# qo-100-i2c-buffer.net
KiCad netlist of a schematic drawn in EAGLE
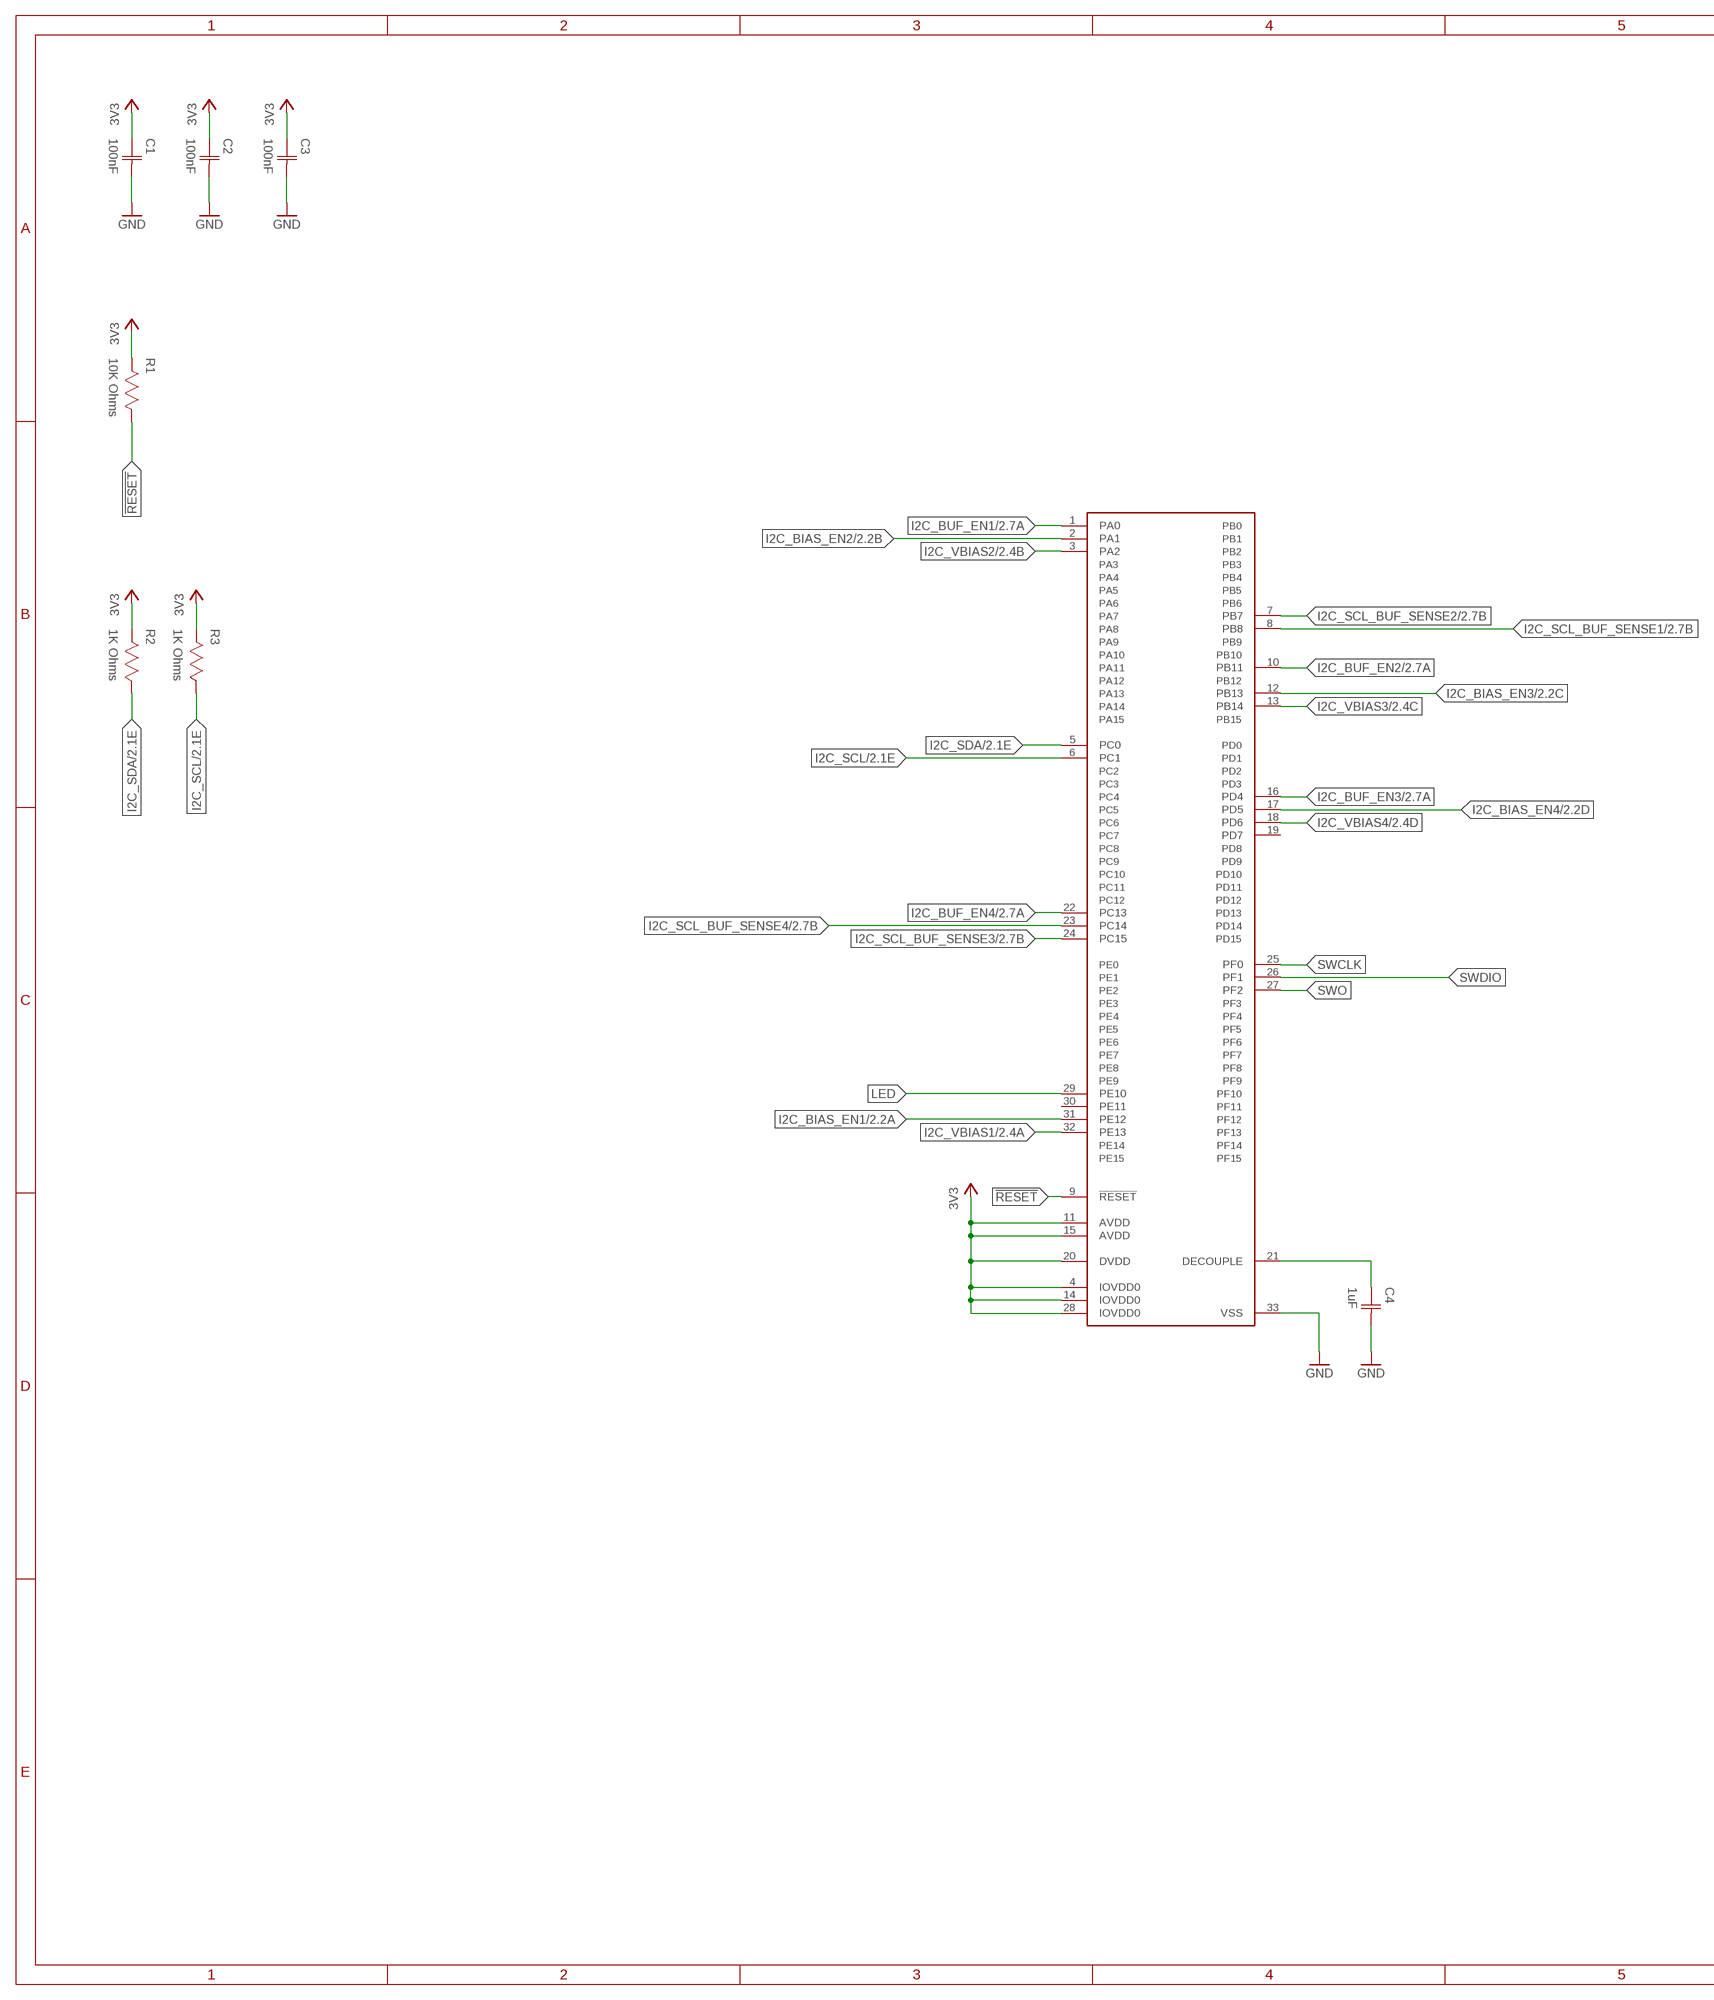
[diagram p0: schematic, sheet 1, part 1 of 2]
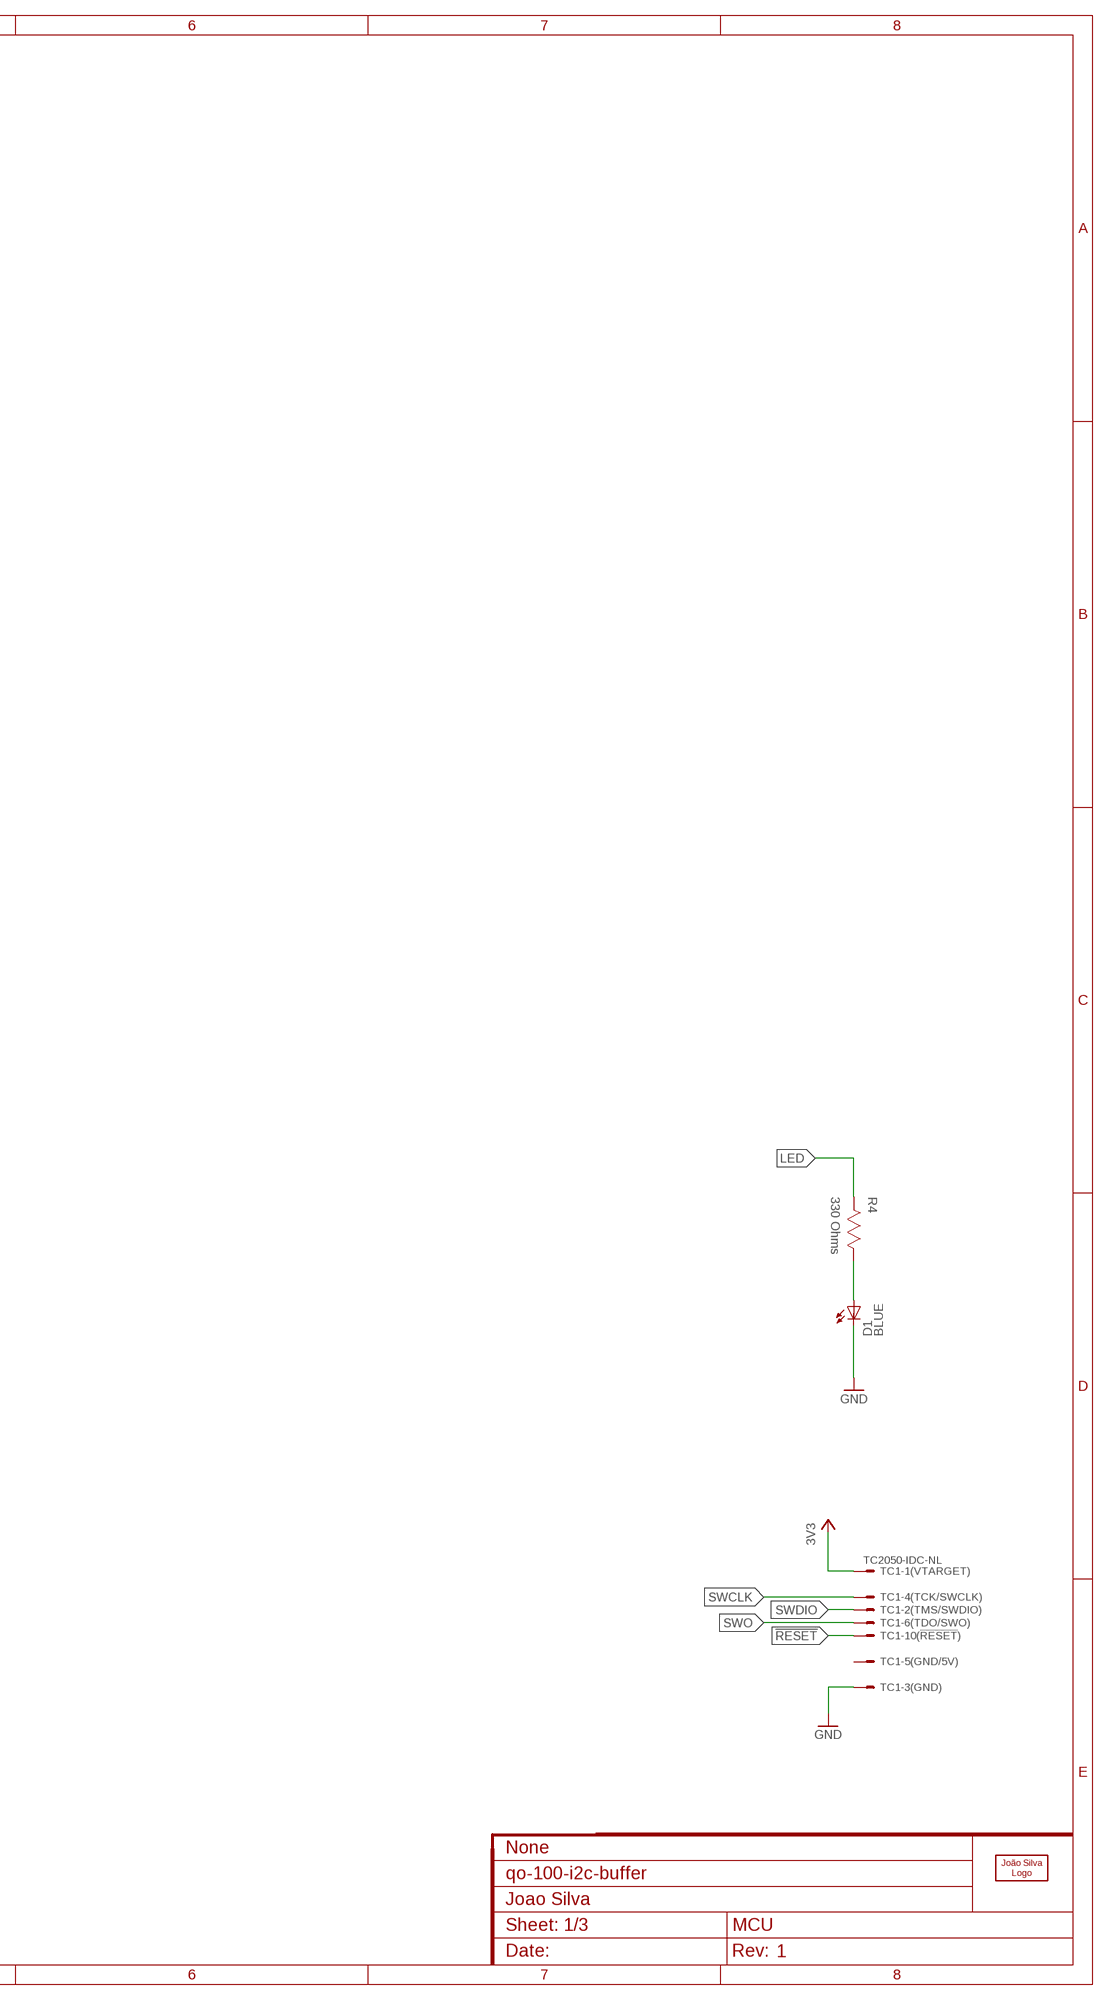
[diagram p1: schematic, sheet 1, part 2 of 2]
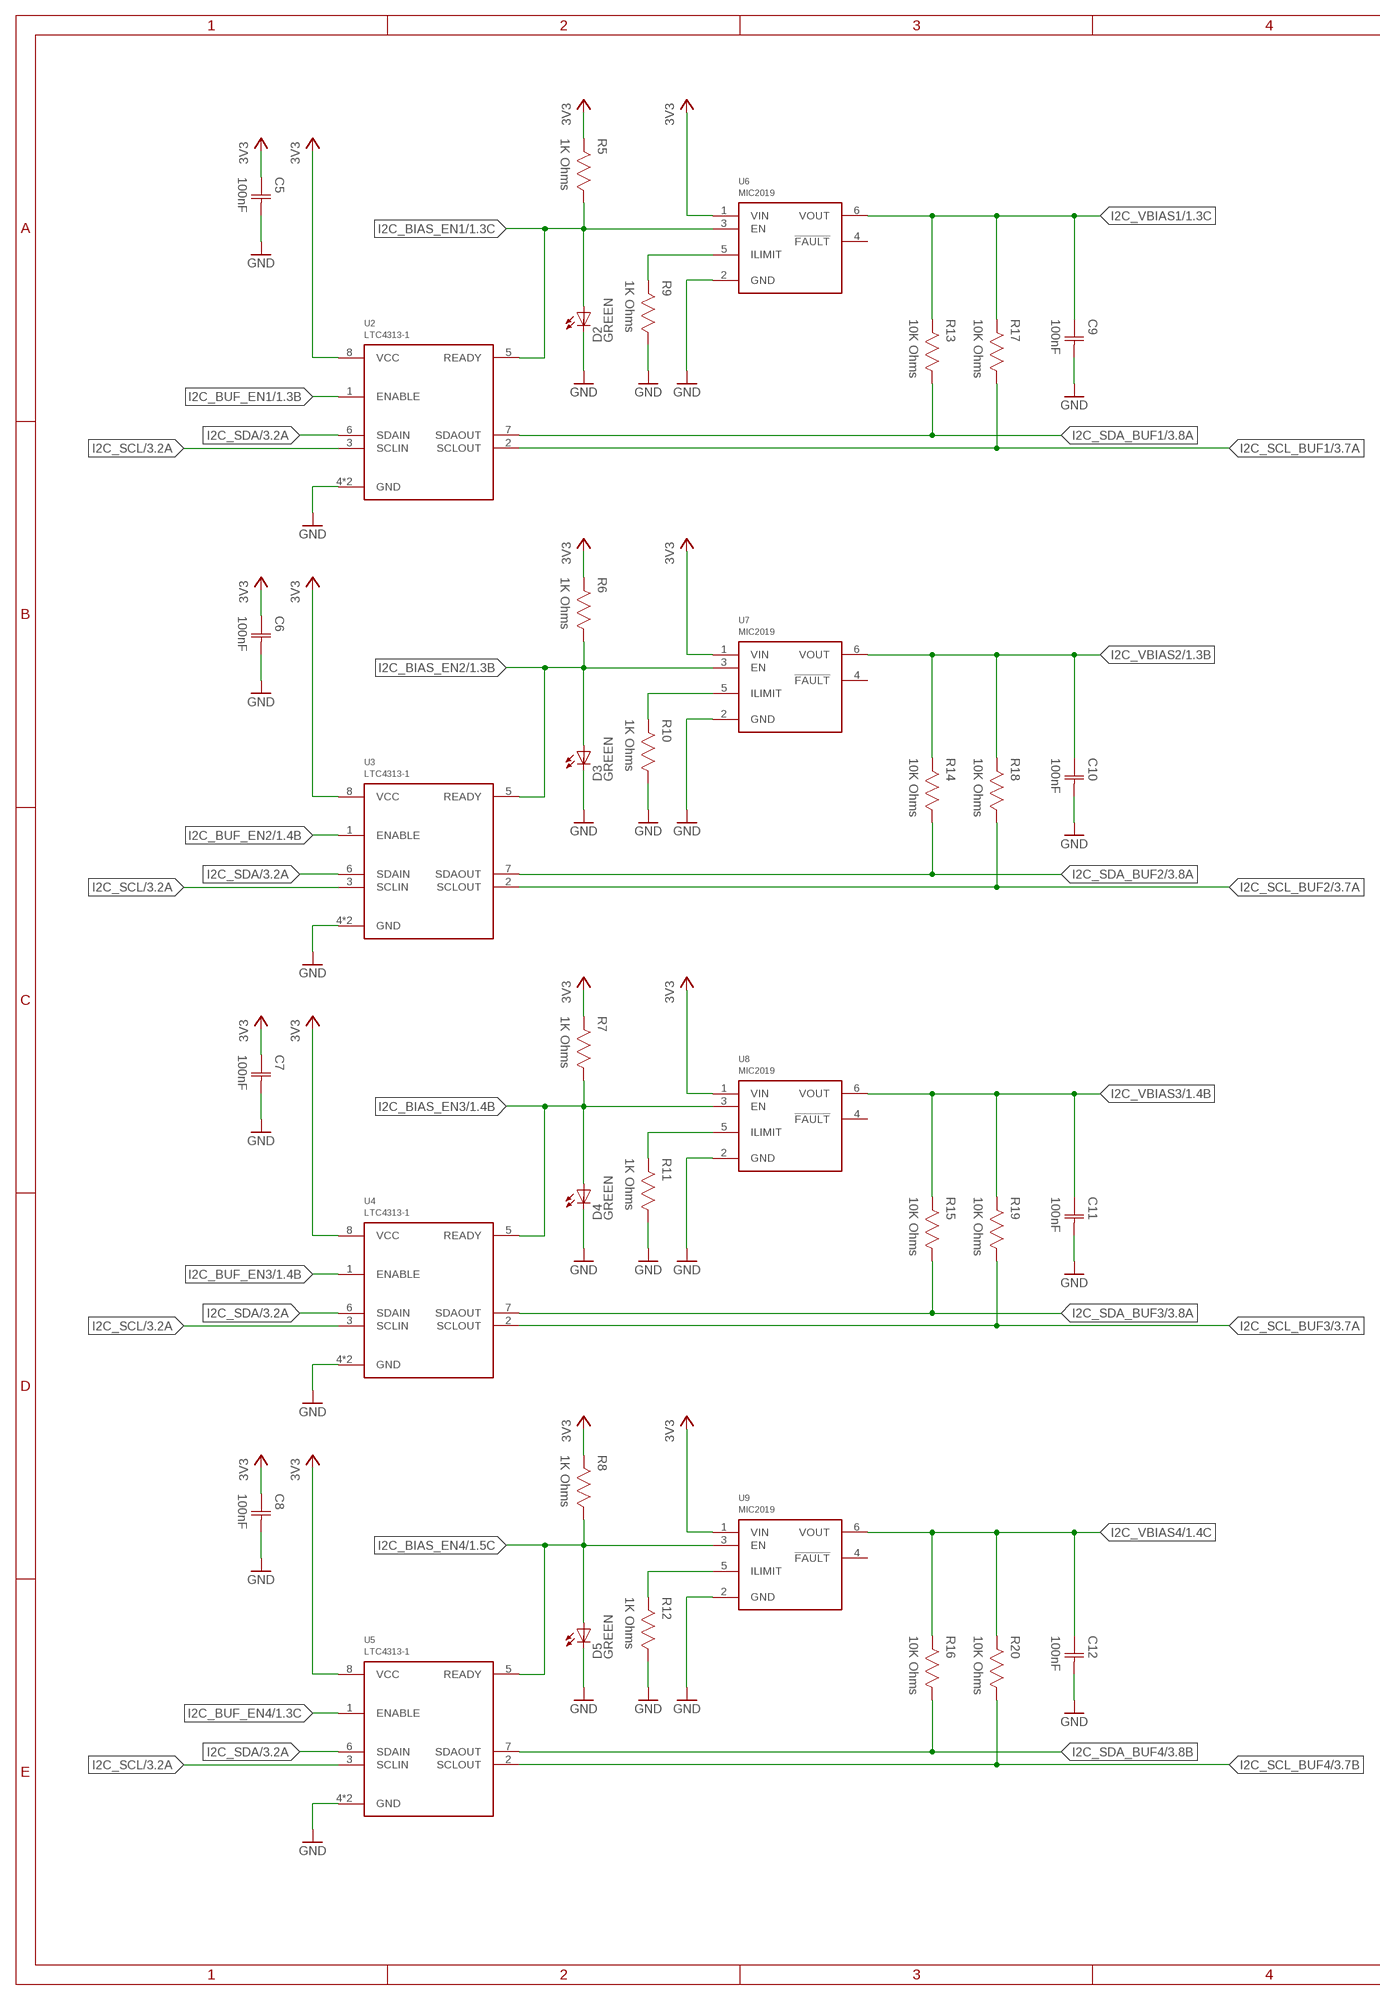
[diagram p2: schematic, sheet 2, part 1 of 2]
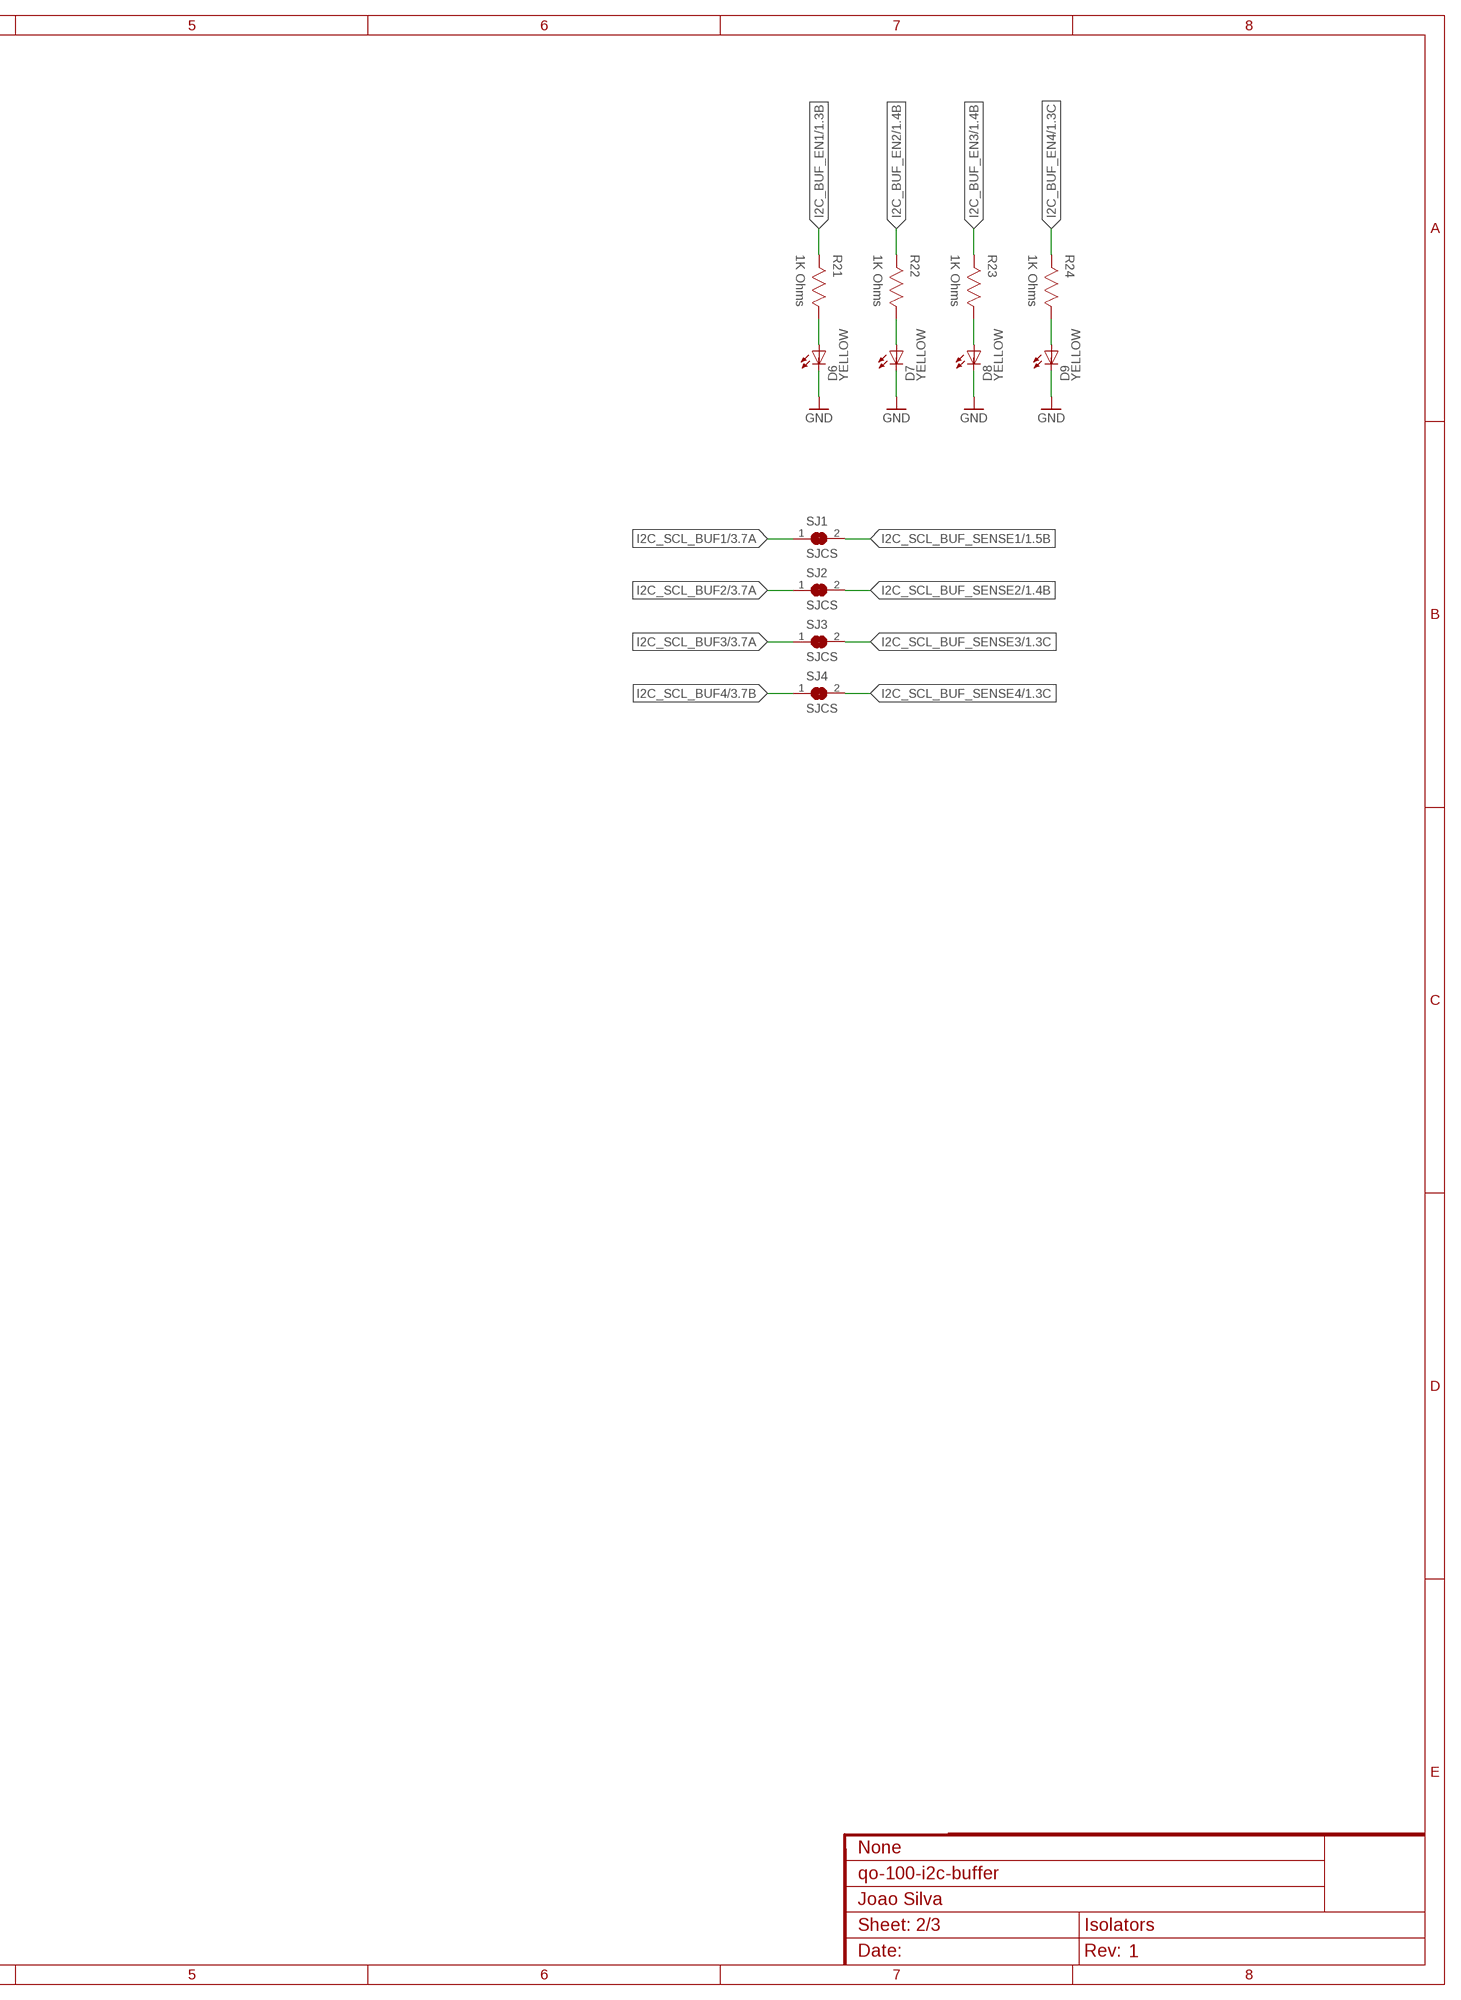
[diagram p3: schematic, sheet 2, part 2 of 2]
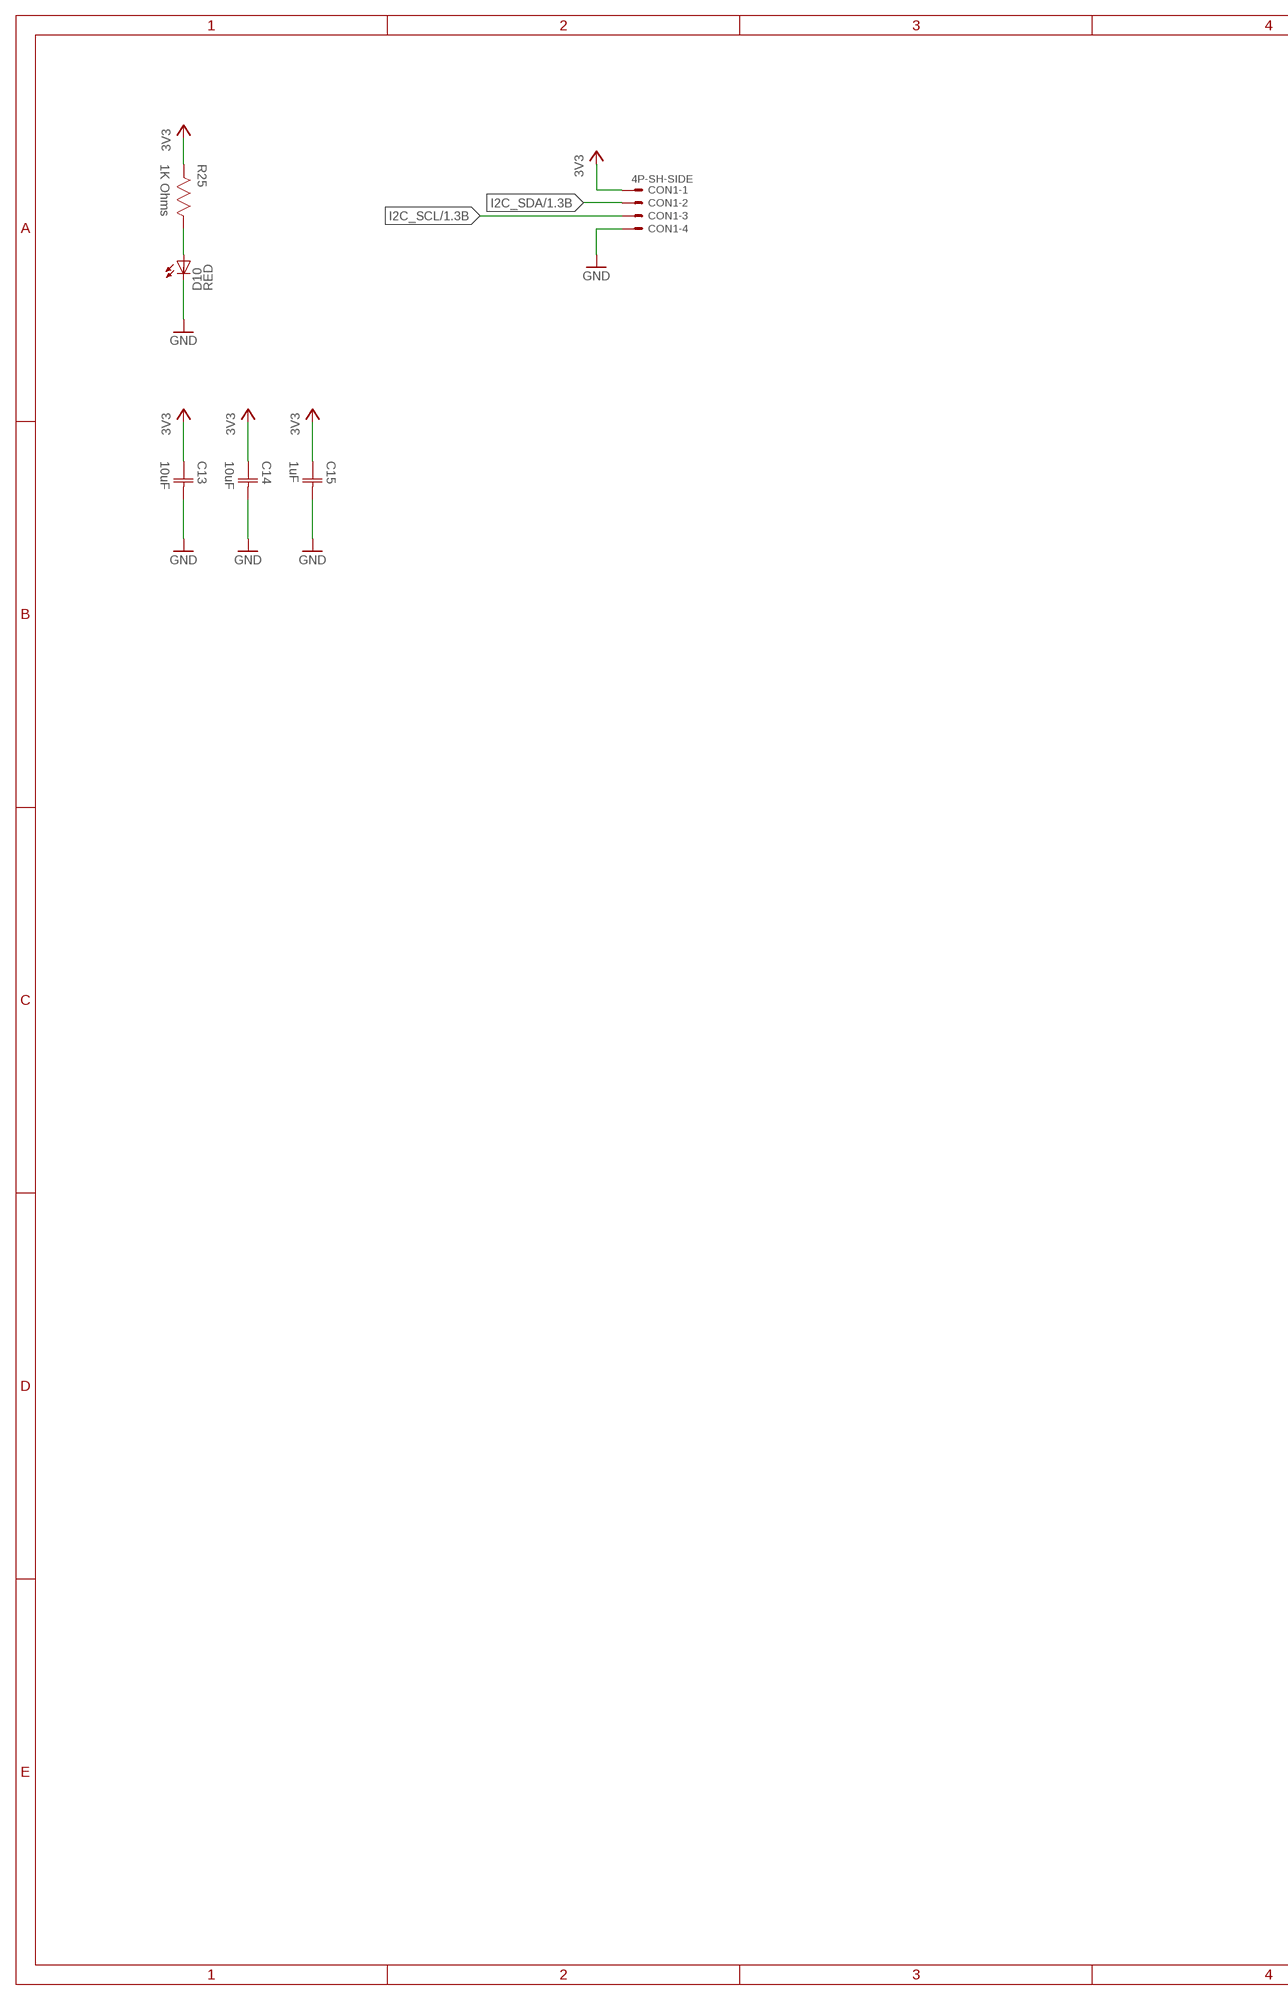
[diagram p4: schematic, sheet 3, part 1 of 2]
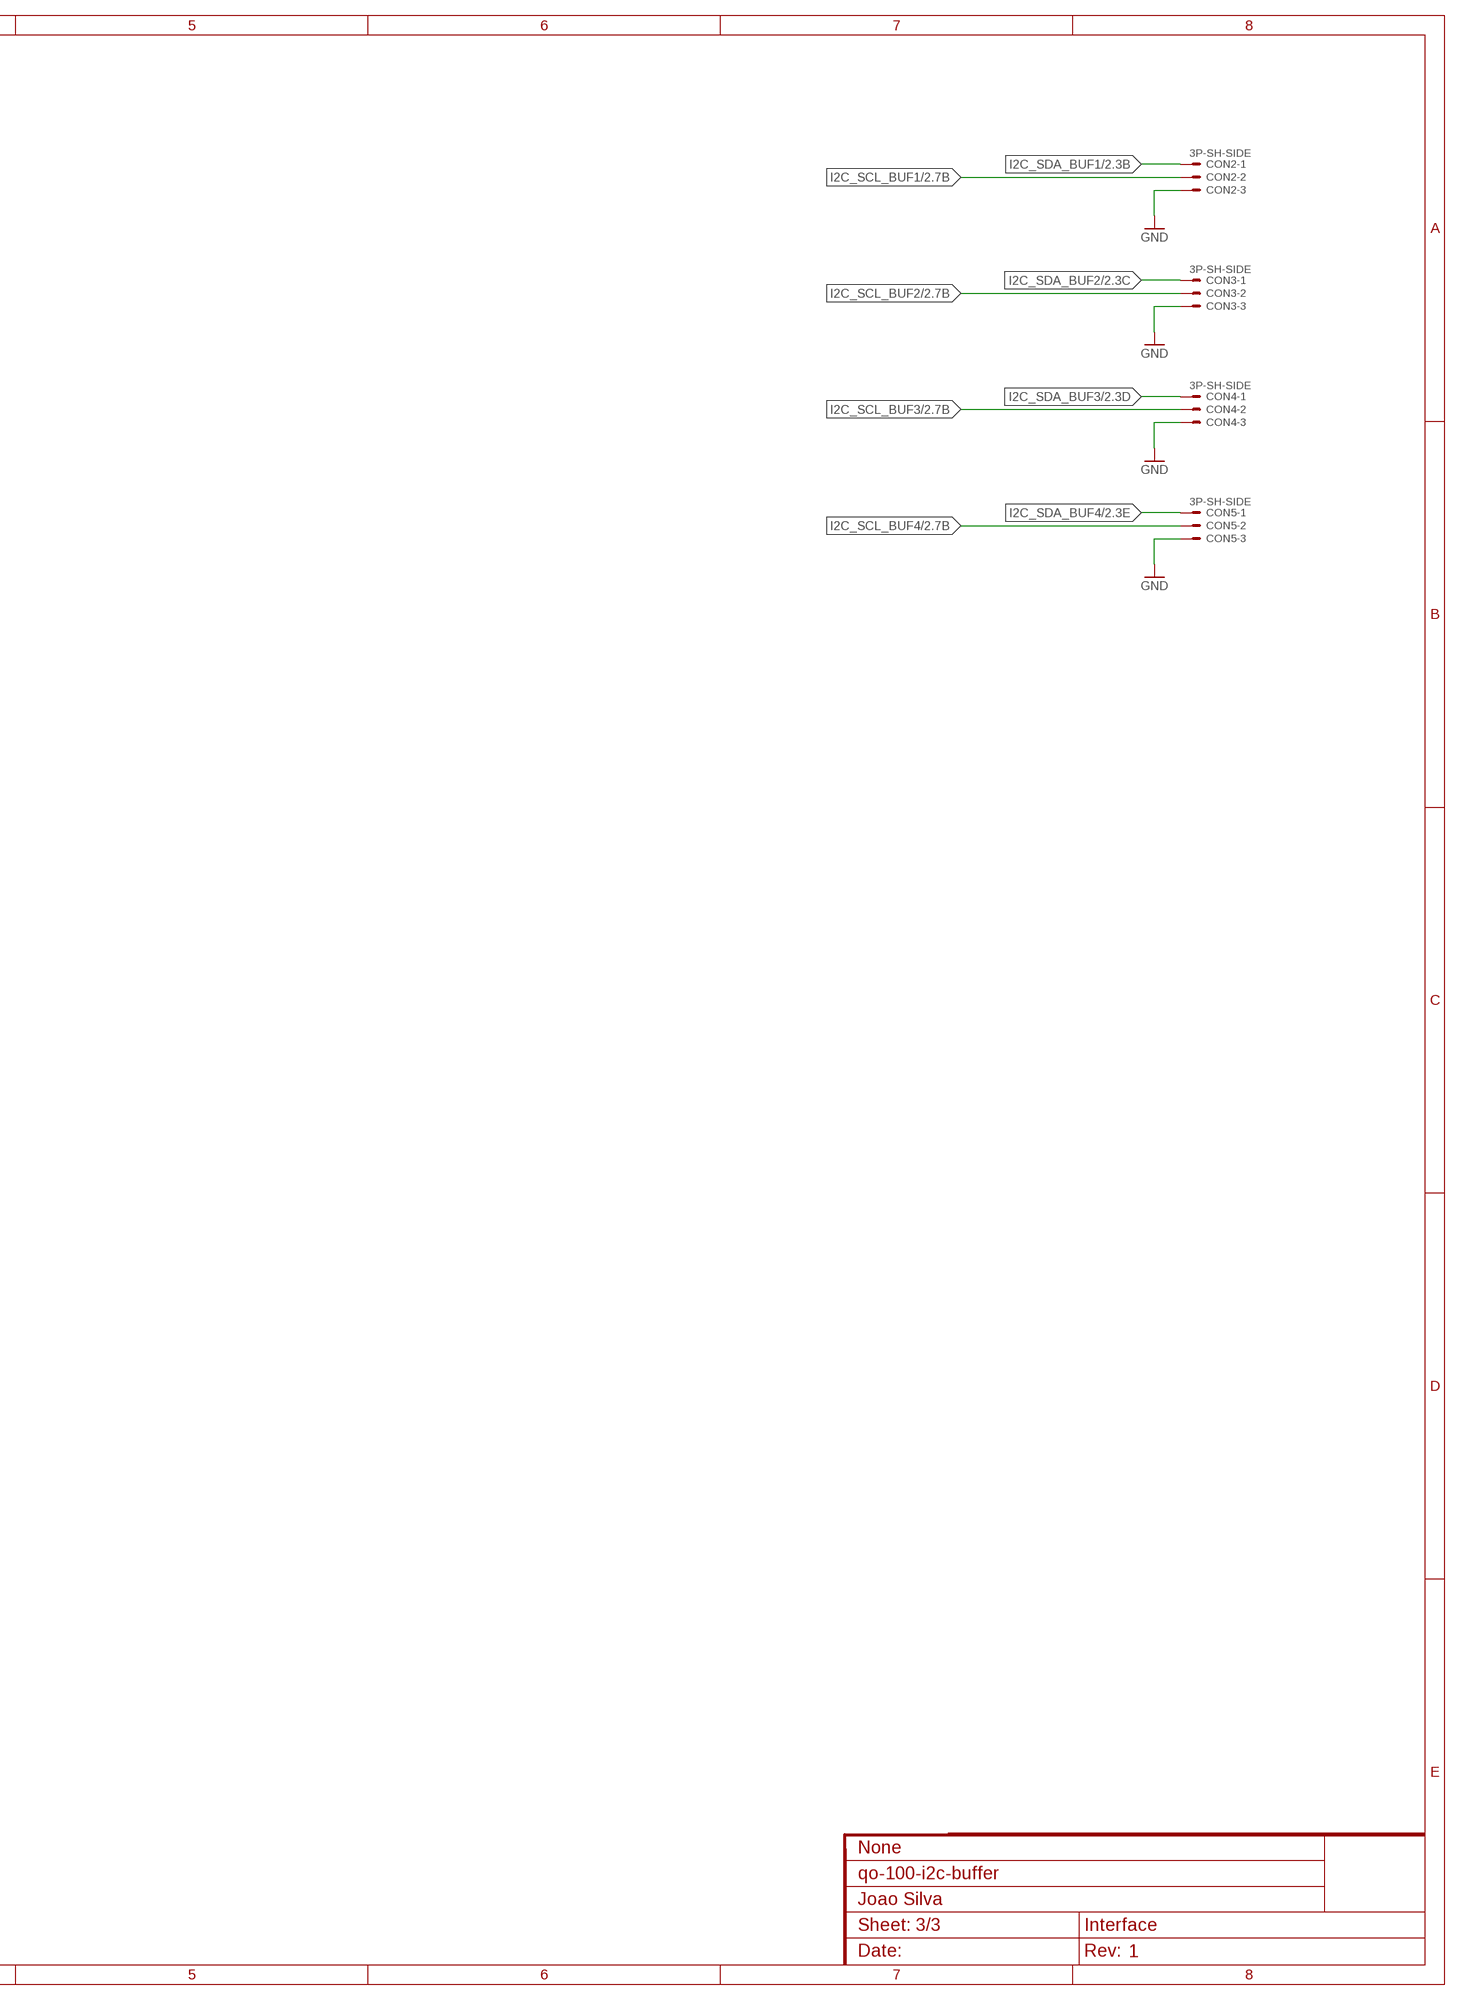
[diagram p5: schematic, sheet 3, part 2 of 2]

(export (version "E")
  (design (tool "Eeschema 10.0.6"))
  (components
    (comp (ref "C5")
      (value "100nF")
      (footprint "eagle-import:CAP0402")
      (libsource (lib "eagle-import") (part "CAPACITOR-0402"))
    )
    (comp (ref "C6")
      (value "100nF")
      (footprint "eagle-import:CAP0402")
      (libsource (lib "eagle-import") (part "CAPACITOR-0402"))
    )
    (comp (ref "C7")
      (value "100nF")
      (footprint "eagle-import:CAP0402")
      (libsource (lib "eagle-import") (part "CAPACITOR-0402"))
    )
    (comp (ref "C8")
      (value "100nF")
      (footprint "eagle-import:CAP0402")
      (libsource (lib "eagle-import") (part "CAPACITOR-0402"))
    )
    (comp (ref "C9")
      (value "100nF")
      (footprint "eagle-import:CAP0402")
      (libsource (lib "eagle-import") (part "CAPACITOR-0402"))
    )
    (comp (ref "C10")
      (value "100nF")
      (footprint "eagle-import:CAP0402")
      (libsource (lib "eagle-import") (part "CAPACITOR-0402"))
    )
    (comp (ref "C11")
      (value "100nF")
      (footprint "eagle-import:CAP0402")
      (libsource (lib "eagle-import") (part "CAPACITOR-0402"))
    )
    (comp (ref "C12")
      (value "100nF")
      (footprint "eagle-import:CAP0402")
      (libsource (lib "eagle-import") (part "CAPACITOR-0402"))
    )
    (comp (ref "D2")
      (value "LED0603")
      (footprint "eagle-import:0603")
      (fields (field (name "COLOR") "GREEN"))
      (libsource (lib "eagle-import") (part "LED0603"))
    )
    (comp (ref "D3")
      (value "LED0603")
      (footprint "eagle-import:0603")
      (fields (field (name "COLOR") "GREEN"))
      (libsource (lib "eagle-import") (part "LED0603"))
    )
    (comp (ref "D4")
      (value "LED0603")
      (footprint "eagle-import:0603")
      (fields (field (name "COLOR") "GREEN"))
      (libsource (lib "eagle-import") (part "LED0603"))
    )
    (comp (ref "D5")
      (value "LED0603")
      (footprint "eagle-import:0603")
      (fields (field (name "COLOR") "GREEN"))
      (libsource (lib "eagle-import") (part "LED0603"))
    )
    (comp (ref "D6")
      (value "LED0603")
      (footprint "eagle-import:0603")
      (fields (field (name "COLOR") "YELLOW"))
      (libsource (lib "eagle-import") (part "LED0603"))
    )
    (comp (ref "D7")
      (value "LED0603")
      (footprint "eagle-import:0603")
      (fields (field (name "COLOR") "YELLOW"))
      (libsource (lib "eagle-import") (part "LED0603"))
    )
    (comp (ref "D8")
      (value "LED0603")
      (footprint "eagle-import:0603")
      (fields (field (name "COLOR") "YELLOW"))
      (libsource (lib "eagle-import") (part "LED0603"))
    )
    (comp (ref "D9")
      (value "LED0603")
      (footprint "eagle-import:0603")
      (fields (field (name "COLOR") "YELLOW"))
      (libsource (lib "eagle-import") (part "LED0603"))
    )
    (comp (ref "R5")
      (value "1K Ohms")
      (footprint "eagle-import:RES0402")
      (libsource (lib "eagle-import") (part "RESISTOR-0402"))
    )
    (comp (ref "R6")
      (value "1K Ohms")
      (footprint "eagle-import:RES0402")
      (libsource (lib "eagle-import") (part "RESISTOR-0402"))
    )
    (comp (ref "R7")
      (value "1K Ohms")
      (footprint "eagle-import:RES0402")
      (libsource (lib "eagle-import") (part "RESISTOR-0402"))
    )
    (comp (ref "R8")
      (value "1K Ohms")
      (footprint "eagle-import:RES0402")
      (libsource (lib "eagle-import") (part "RESISTOR-0402"))
    )
    (comp (ref "R9")
      (value "1K Ohms")
      (footprint "eagle-import:RES0402")
      (libsource (lib "eagle-import") (part "RESISTOR-0402"))
    )
    (comp (ref "R10")
      (value "1K Ohms")
      (footprint "eagle-import:RES0402")
      (libsource (lib "eagle-import") (part "RESISTOR-0402"))
    )
    (comp (ref "R11")
      (value "1K Ohms")
      (footprint "eagle-import:RES0402")
      (libsource (lib "eagle-import") (part "RESISTOR-0402"))
    )
    (comp (ref "R12")
      (value "1K Ohms")
      (footprint "eagle-import:RES0402")
      (libsource (lib "eagle-import") (part "RESISTOR-0402"))
    )
    (comp (ref "R13")
      (value "10K Ohms")
      (footprint "eagle-import:RES0402")
      (libsource (lib "eagle-import") (part "RESISTOR-0402"))
    )
    (comp (ref "R14")
      (value "10K Ohms")
      (footprint "eagle-import:RES0402")
      (libsource (lib "eagle-import") (part "RESISTOR-0402"))
    )
    (comp (ref "R15")
      (value "10K Ohms")
      (footprint "eagle-import:RES0402")
      (libsource (lib "eagle-import") (part "RESISTOR-0402"))
    )
    (comp (ref "R16")
      (value "10K Ohms")
      (footprint "eagle-import:RES0402")
      (libsource (lib "eagle-import") (part "RESISTOR-0402"))
    )
    (comp (ref "R17")
      (value "10K Ohms")
      (footprint "eagle-import:RES0402")
      (libsource (lib "eagle-import") (part "RESISTOR-0402"))
    )
    (comp (ref "R18")
      (value "10K Ohms")
      (footprint "eagle-import:RES0402")
      (libsource (lib "eagle-import") (part "RESISTOR-0402"))
    )
    (comp (ref "R19")
      (value "10K Ohms")
      (footprint "eagle-import:RES0402")
      (libsource (lib "eagle-import") (part "RESISTOR-0402"))
    )
    (comp (ref "R20")
      (value "10K Ohms")
      (footprint "eagle-import:RES0402")
      (libsource (lib "eagle-import") (part "RESISTOR-0402"))
    )
    (comp (ref "R21")
      (value "1K Ohms")
      (footprint "eagle-import:RES0402")
      (libsource (lib "eagle-import") (part "RESISTOR-0402"))
    )
    (comp (ref "R22")
      (value "1K Ohms")
      (footprint "eagle-import:RES0402")
      (libsource (lib "eagle-import") (part "RESISTOR-0402"))
    )
    (comp (ref "R23")
      (value "1K Ohms")
      (footprint "eagle-import:RES0402")
      (libsource (lib "eagle-import") (part "RESISTOR-0402"))
    )
    (comp (ref "R24")
      (value "1K Ohms")
      (footprint "eagle-import:RES0402")
      (libsource (lib "eagle-import") (part "RESISTOR-0402"))
    )
    (comp (ref "SJ1")
      (value "SJCS")
      (footprint "eagle-import:SJC_S")
      (libsource (lib "eagle-import") (part "SJCS"))
    )
    (comp (ref "SJ2")
      (value "SJCS")
      (footprint "eagle-import:SJC_S")
      (libsource (lib "eagle-import") (part "SJCS"))
    )
    (comp (ref "SJ3")
      (value "SJCS")
      (footprint "eagle-import:SJC_S")
      (libsource (lib "eagle-import") (part "SJCS"))
    )
    (comp (ref "SJ4")
      (value "SJCS")
      (footprint "eagle-import:SJC_S")
      (libsource (lib "eagle-import") (part "SJCS"))
    )
    (comp (ref "U2")
      (value "LTC4313-1")
      (footprint "eagle-import:DFN8")
      (libsource (lib "eagle-import") (part "LTC4313-1"))
    )
    (comp (ref "U3")
      (value "LTC4313-1")
      (footprint "eagle-import:DFN8")
      (libsource (lib "eagle-import") (part "LTC4313-1"))
    )
    (comp (ref "U4")
      (value "LTC4313-1")
      (footprint "eagle-import:DFN8")
      (libsource (lib "eagle-import") (part "LTC4313-1"))
    )
    (comp (ref "U5")
      (value "LTC4313-1")
      (footprint "eagle-import:DFN8")
      (libsource (lib "eagle-import") (part "LTC4313-1"))
    )
    (comp (ref "U6")
      (value "MIC2019")
      (footprint "eagle-import:SOT23-6")
      (libsource (lib "eagle-import") (part "MIC2091"))
    )
    (comp (ref "U7")
      (value "MIC2019")
      (footprint "eagle-import:SOT23-6")
      (libsource (lib "eagle-import") (part "MIC2091"))
    )
    (comp (ref "U8")
      (value "MIC2019")
      (footprint "eagle-import:SOT23-6")
      (libsource (lib "eagle-import") (part "MIC2091"))
    )
    (comp (ref "U9")
      (value "MIC2019")
      (footprint "eagle-import:SOT23-6")
      (libsource (lib "eagle-import") (part "MIC2091"))
    )
    (comp (ref "C1")
      (value "100nF")
      (footprint "eagle-import:CAP0402")
      (libsource (lib "eagle-import") (part "CAPACITOR-0402"))
    )
    (comp (ref "C2")
      (value "100nF")
      (footprint "eagle-import:CAP0402")
      (libsource (lib "eagle-import") (part "CAPACITOR-0402"))
    )
    (comp (ref "C3")
      (value "100nF")
      (footprint "eagle-import:CAP0402")
      (libsource (lib "eagle-import") (part "CAPACITOR-0402"))
    )
    (comp (ref "C4")
      (value "1uF")
      (footprint "eagle-import:CAP0402")
      (libsource (lib "eagle-import") (part "CAPACITOR-0402"))
    )
    (comp (ref "D1")
      (value "LED0603")
      (footprint "eagle-import:0603")
      (fields (field (name "COLOR") "BLUE"))
      (libsource (lib "eagle-import") (part "LED0603"))
    )
    (comp (ref "LOGO1")
      (value "JS-5MM")
      (footprint "eagle-import:JS_5MM")
      (libsource (lib "eagle-import") (part "JS-5MM"))
    )
    (comp (ref "R1")
      (value "10K Ohms")
      (footprint "eagle-import:RES0402")
      (libsource (lib "eagle-import") (part "RESISTOR-0402"))
    )
    (comp (ref "R2")
      (value "1K Ohms")
      (footprint "eagle-import:RES0402")
      (libsource (lib "eagle-import") (part "RESISTOR-0402"))
    )
    (comp (ref "R3")
      (value "1K Ohms")
      (footprint "eagle-import:RES0402")
      (libsource (lib "eagle-import") (part "RESISTOR-0402"))
    )
    (comp (ref "R4")
      (value "330 Ohms")
      (footprint "eagle-import:RES0402")
      (libsource (lib "eagle-import") (part "RESISTOR-0402"))
    )
    (comp (ref "TC1")
      (value "TC2050-IDC-NL")
      (footprint "eagle-import:TC2050-IDC-NL")
      (libsource (lib "eagle-import") (part "TC2050-IDC-NL"))
    )
    (comp (ref "U1")
      (value "EFM32TG11B120F128GM32")
      (footprint "eagle-import:QFN32_0.5P_TG")
      (libsource (lib "eagle-import") (part "EFM32TG11B1M3220F128G"))
    )
    (comp (ref "C13")
      (value "10uF")
      (footprint "eagle-import:CAP0603")
      (libsource (lib "eagle-import") (part "CAPACITOR-0603"))
    )
    (comp (ref "C14")
      (value "10uF")
      (footprint "eagle-import:CAP0603")
      (libsource (lib "eagle-import") (part "CAPACITOR-0603"))
    )
    (comp (ref "C15")
      (value "1uF")
      (footprint "eagle-import:CAP0402")
      (libsource (lib "eagle-import") (part "CAPACITOR-0402"))
    )
    (comp (ref "CON1")
      (value "4P-SH-SIDE")
      (footprint "eagle-import:SH-04-SIDE")
      (libsource (lib "eagle-import") (part "4P-SH-SIDE"))
    )
    (comp (ref "CON2")
      (value "3P-SH-SIDE")
      (footprint "eagle-import:SH-03-SIDE")
      (libsource (lib "eagle-import") (part "3P-SH-SIDE"))
    )
    (comp (ref "CON3")
      (value "3P-SH-SIDE")
      (footprint "eagle-import:SH-03-SIDE")
      (libsource (lib "eagle-import") (part "3P-SH-SIDE"))
    )
    (comp (ref "CON4")
      (value "3P-SH-SIDE")
      (footprint "eagle-import:SH-03-SIDE")
      (libsource (lib "eagle-import") (part "3P-SH-SIDE"))
    )
    (comp (ref "CON5")
      (value "3P-SH-SIDE")
      (footprint "eagle-import:SH-03-SIDE")
      (libsource (lib "eagle-import") (part "3P-SH-SIDE"))
    )
    (comp (ref "D10")
      (value "LED0603")
      (footprint "eagle-import:0603")
      (fields (field (name "COLOR") "RED"))
      (libsource (lib "eagle-import") (part "LED0603"))
    )
    (comp (ref "R25")
      (value "1K Ohms")
      (footprint "eagle-import:RES0402")
      (libsource (lib "eagle-import") (part "RESISTOR-0402"))
    )
  )
  (nets
    (net (code "1") (name "3V3") (class "Default")
      (node (ref "C1") (pin "1") (pinfunction "C1_1") (pintype "passive"))
      (node (ref "C13") (pin "1") (pinfunction "C1_1") (pintype "passive"))
      (node (ref "C14") (pin "1") (pinfunction "C1_1") (pintype "passive"))
      (node (ref "C15") (pin "1") (pinfunction "C1_1") (pintype "passive"))
      (node (ref "C2") (pin "1") (pinfunction "C1_1") (pintype "passive"))
      (node (ref "C3") (pin "1") (pinfunction "C1_1") (pintype "passive"))
      (node (ref "C5") (pin "1") (pinfunction "C1_1") (pintype "passive"))
      (node (ref "C6") (pin "1") (pinfunction "C1_1") (pintype "passive"))
      (node (ref "C7") (pin "1") (pinfunction "C1_1") (pintype "passive"))
      (node (ref "C8") (pin "1") (pinfunction "C1_1") (pintype "passive"))
      (node (ref "CON1") (pin "1") (pinfunction "S_1") (pintype "passive"))
      (node (ref "R1") (pin "2") (pinfunction "2_2") (pintype "passive"))
      (node (ref "R2") (pin "2") (pinfunction "2_2") (pintype "passive"))
      (node (ref "R25") (pin "2") (pinfunction "2_2") (pintype "passive"))
      (node (ref "R3") (pin "2") (pinfunction "2_2") (pintype "passive"))
      (node (ref "R5") (pin "2") (pinfunction "2_2") (pintype "passive"))
      (node (ref "R6") (pin "2") (pinfunction "2_2") (pintype "passive"))
      (node (ref "R7") (pin "2") (pinfunction "2_2") (pintype "passive"))
      (node (ref "R8") (pin "2") (pinfunction "2_2") (pintype "passive"))
      (node (ref "TC1") (pin "1") (pinfunction "S_1") (pintype "passive"))
      (node (ref "U1") (pin "11") (pinfunction "AVDD_11") (pintype "bidirectional"))
      (node (ref "U1") (pin "14") (pinfunction "IOVDD0_14") (pintype "bidirectional"))
      (node (ref "U1") (pin "15") (pinfunction "AVDD_15") (pintype "bidirectional"))
      (node (ref "U1") (pin "20") (pinfunction "DVDD_20") (pintype "bidirectional"))
      (node (ref "U1") (pin "28") (pinfunction "IOVDD0_28") (pintype "bidirectional"))
      (node (ref "U1") (pin "4") (pinfunction "IOVDD0_4") (pintype "bidirectional"))
      (node (ref "U2") (pin "8") (pinfunction "VCC_8") (pintype "bidirectional"))
      (node (ref "U3") (pin "8") (pinfunction "VCC_8") (pintype "bidirectional"))
      (node (ref "U4") (pin "8") (pinfunction "VCC_8") (pintype "bidirectional"))
      (node (ref "U5") (pin "8") (pinfunction "VCC_8") (pintype "bidirectional"))
      (node (ref "U6") (pin "1") (pinfunction "VIN_1") (pintype "bidirectional"))
      (node (ref "U7") (pin "1") (pinfunction "VIN_1") (pintype "bidirectional"))
      (node (ref "U8") (pin "1") (pinfunction "VIN_1") (pintype "bidirectional"))
      (node (ref "U9") (pin "1") (pinfunction "VIN_1") (pintype "bidirectional"))
    )
    (net (code "2") (name "GND") (class "Default")
      (node (ref "C1") (pin "2") (pinfunction "C2_2") (pintype "passive"))
      (node (ref "C10") (pin "2") (pinfunction "C2_2") (pintype "passive"))
      (node (ref "C11") (pin "2") (pinfunction "C2_2") (pintype "passive"))
      (node (ref "C12") (pin "2") (pinfunction "C2_2") (pintype "passive"))
      (node (ref "C13") (pin "2") (pinfunction "C2_2") (pintype "passive"))
      (node (ref "C14") (pin "2") (pinfunction "C2_2") (pintype "passive"))
      (node (ref "C15") (pin "2") (pinfunction "C2_2") (pintype "passive"))
      (node (ref "C2") (pin "2") (pinfunction "C2_2") (pintype "passive"))
      (node (ref "C3") (pin "2") (pinfunction "C2_2") (pintype "passive"))
      (node (ref "C4") (pin "2") (pinfunction "C2_2") (pintype "passive"))
      (node (ref "C5") (pin "2") (pinfunction "C2_2") (pintype "passive"))
      (node (ref "C6") (pin "2") (pinfunction "C2_2") (pintype "passive"))
      (node (ref "C7") (pin "2") (pinfunction "C2_2") (pintype "passive"))
      (node (ref "C8") (pin "2") (pinfunction "C2_2") (pintype "passive"))
      (node (ref "C9") (pin "2") (pinfunction "C2_2") (pintype "passive"))
      (node (ref "CON1") (pin "4") (pinfunction "S_4") (pintype "passive"))
      (node (ref "CON2") (pin "3") (pinfunction "S_3") (pintype "passive"))
      (node (ref "CON3") (pin "3") (pinfunction "S_3") (pintype "passive"))
      (node (ref "CON4") (pin "3") (pinfunction "S_3") (pintype "passive"))
      (node (ref "CON5") (pin "3") (pinfunction "S_3") (pintype "passive"))
      (node (ref "D1") (pin "C") (pinfunction "C_C") (pintype "passive"))
      (node (ref "D10") (pin "C") (pinfunction "C_C") (pintype "passive"))
      (node (ref "D2") (pin "C") (pinfunction "C_C") (pintype "passive"))
      (node (ref "D3") (pin "C") (pinfunction "C_C") (pintype "passive"))
      (node (ref "D4") (pin "C") (pinfunction "C_C") (pintype "passive"))
      (node (ref "D5") (pin "C") (pinfunction "C_C") (pintype "passive"))
      (node (ref "D6") (pin "C") (pinfunction "C_C") (pintype "passive"))
      (node (ref "D7") (pin "C") (pinfunction "C_C") (pintype "passive"))
      (node (ref "D8") (pin "C") (pinfunction "C_C") (pintype "passive"))
      (node (ref "D9") (pin "C") (pinfunction "C_C") (pintype "passive"))
      (node (ref "R10") (pin "1") (pinfunction "1_1") (pintype "passive"))
      (node (ref "R11") (pin "1") (pinfunction "1_1") (pintype "passive"))
      (node (ref "R12") (pin "1") (pinfunction "1_1") (pintype "passive"))
      (node (ref "R9") (pin "1") (pinfunction "1_1") (pintype "passive"))
      (node (ref "TC1") (pin "3") (pinfunction "S_3") (pintype "passive"))
      (node (ref "U1") (pin "33") (pinfunction "VSS_33") (pintype "bidirectional"))
      (node (ref "U2") (pin "4") (pinfunction "GND_4") (pintype "bidirectional"))
      (node (ref "U2") (pin "9") (pinfunction "GND_9") (pintype "bidirectional"))
      (node (ref "U3") (pin "4") (pinfunction "GND_4") (pintype "bidirectional"))
      (node (ref "U3") (pin "9") (pinfunction "GND_9") (pintype "bidirectional"))
      (node (ref "U4") (pin "4") (pinfunction "GND_4") (pintype "bidirectional"))
      (node (ref "U4") (pin "9") (pinfunction "GND_9") (pintype "bidirectional"))
      (node (ref "U5") (pin "4") (pinfunction "GND_4") (pintype "bidirectional"))
      (node (ref "U5") (pin "9") (pinfunction "GND_9") (pintype "bidirectional"))
      (node (ref "U6") (pin "2") (pinfunction "GND_2") (pintype "bidirectional"))
      (node (ref "U7") (pin "2") (pinfunction "GND_2") (pintype "bidirectional"))
      (node (ref "U8") (pin "2") (pinfunction "GND_2") (pintype "bidirectional"))
      (node (ref "U9") (pin "2") (pinfunction "GND_2") (pintype "bidirectional"))
    )
    (net (code "3") (name "I2C_BIAS_EN1") (class "Default")
      (node (ref "D2") (pin "A") (pinfunction "A_A") (pintype "passive"))
      (node (ref "R5") (pin "1") (pinfunction "1_1") (pintype "passive"))
      (node (ref "U1") (pin "31") (pinfunction "PE12_31") (pintype "bidirectional"))
      (node (ref "U2") (pin "5") (pinfunction "READY_5") (pintype "bidirectional"))
      (node (ref "U6") (pin "3") (pinfunction "EN_3") (pintype "bidirectional"))
    )
    (net (code "4") (name "I2C_BIAS_EN2") (class "Default")
      (node (ref "D3") (pin "A") (pinfunction "A_A") (pintype "passive"))
      (node (ref "R6") (pin "1") (pinfunction "1_1") (pintype "passive"))
      (node (ref "U1") (pin "2") (pinfunction "PA1_2") (pintype "bidirectional"))
      (node (ref "U3") (pin "5") (pinfunction "READY_5") (pintype "bidirectional"))
      (node (ref "U7") (pin "3") (pinfunction "EN_3") (pintype "bidirectional"))
    )
    (net (code "5") (name "I2C_BIAS_EN3") (class "Default")
      (node (ref "D4") (pin "A") (pinfunction "A_A") (pintype "passive"))
      (node (ref "R7") (pin "1") (pinfunction "1_1") (pintype "passive"))
      (node (ref "U1") (pin "12") (pinfunction "PB13_12") (pintype "bidirectional"))
      (node (ref "U4") (pin "5") (pinfunction "READY_5") (pintype "bidirectional"))
      (node (ref "U8") (pin "3") (pinfunction "EN_3") (pintype "bidirectional"))
    )
    (net (code "6") (name "I2C_BIAS_EN4") (class "Default")
      (node (ref "D5") (pin "A") (pinfunction "A_A") (pintype "passive"))
      (node (ref "R8") (pin "1") (pinfunction "1_1") (pintype "passive"))
      (node (ref "U1") (pin "17") (pinfunction "PD5_17") (pintype "bidirectional"))
      (node (ref "U5") (pin "5") (pinfunction "READY_5") (pintype "bidirectional"))
      (node (ref "U9") (pin "3") (pinfunction "EN_3") (pintype "bidirectional"))
    )
    (net (code "7") (name "I2C_BUF_EN1") (class "Default")
      (node (ref "R21") (pin "2") (pinfunction "2_2") (pintype "passive"))
      (node (ref "U1") (pin "1") (pinfunction "PA0_1") (pintype "bidirectional"))
      (node (ref "U2") (pin "1") (pinfunction "ENABLE_1") (pintype "bidirectional"))
    )
    (net (code "8") (name "I2C_BUF_EN2") (class "Default")
      (node (ref "R22") (pin "2") (pinfunction "2_2") (pintype "passive"))
      (node (ref "U1") (pin "10") (pinfunction "PB11_10") (pintype "bidirectional"))
      (node (ref "U3") (pin "1") (pinfunction "ENABLE_1") (pintype "bidirectional"))
    )
    (net (code "9") (name "I2C_BUF_EN3") (class "Default")
      (node (ref "R23") (pin "2") (pinfunction "2_2") (pintype "passive"))
      (node (ref "U1") (pin "16") (pinfunction "PD4_16") (pintype "bidirectional"))
      (node (ref "U4") (pin "1") (pinfunction "ENABLE_1") (pintype "bidirectional"))
    )
    (net (code "10") (name "I2C_BUF_EN4") (class "Default")
      (node (ref "R24") (pin "2") (pinfunction "2_2") (pintype "passive"))
      (node (ref "U1") (pin "22") (pinfunction "PC13_22") (pintype "bidirectional"))
      (node (ref "U5") (pin "1") (pinfunction "ENABLE_1") (pintype "bidirectional"))
    )
    (net (code "11") (name "I2C_SCL") (class "Default")
      (node (ref "CON1") (pin "3") (pinfunction "S_3") (pintype "passive"))
      (node (ref "R3") (pin "1") (pinfunction "1_1") (pintype "passive"))
      (node (ref "U1") (pin "6") (pinfunction "PC1_6") (pintype "bidirectional"))
      (node (ref "U2") (pin "3") (pinfunction "SCLIN_3") (pintype "bidirectional"))
      (node (ref "U3") (pin "3") (pinfunction "SCLIN_3") (pintype "bidirectional"))
      (node (ref "U4") (pin "3") (pinfunction "SCLIN_3") (pintype "bidirectional"))
      (node (ref "U5") (pin "3") (pinfunction "SCLIN_3") (pintype "bidirectional"))
    )
    (net (code "12") (name "I2C_SCL_BUF1") (class "Default")
      (node (ref "CON2") (pin "2") (pinfunction "S_2") (pintype "passive"))
      (node (ref "R17") (pin "1") (pinfunction "1_1") (pintype "passive"))
      (node (ref "SJ1") (pin "1") (pinfunction "1_1") (pintype "passive"))
      (node (ref "U2") (pin "2") (pinfunction "SCLOUT_2") (pintype "bidirectional"))
    )
    (net (code "13") (name "I2C_SCL_BUF2") (class "Default")
      (node (ref "CON3") (pin "2") (pinfunction "S_2") (pintype "passive"))
      (node (ref "R18") (pin "1") (pinfunction "1_1") (pintype "passive"))
      (node (ref "SJ2") (pin "1") (pinfunction "1_1") (pintype "passive"))
      (node (ref "U3") (pin "2") (pinfunction "SCLOUT_2") (pintype "bidirectional"))
    )
    (net (code "14") (name "I2C_SCL_BUF3") (class "Default")
      (node (ref "CON4") (pin "2") (pinfunction "S_2") (pintype "passive"))
      (node (ref "R19") (pin "1") (pinfunction "1_1") (pintype "passive"))
      (node (ref "SJ3") (pin "1") (pinfunction "1_1") (pintype "passive"))
      (node (ref "U4") (pin "2") (pinfunction "SCLOUT_2") (pintype "bidirectional"))
    )
    (net (code "15") (name "I2C_SCL_BUF4") (class "Default")
      (node (ref "CON5") (pin "2") (pinfunction "S_2") (pintype "passive"))
      (node (ref "R20") (pin "1") (pinfunction "1_1") (pintype "passive"))
      (node (ref "SJ4") (pin "1") (pinfunction "1_1") (pintype "passive"))
      (node (ref "U5") (pin "2") (pinfunction "SCLOUT_2") (pintype "bidirectional"))
    )
    (net (code "16") (name "I2C_SCL_BUF_SENSE1") (class "Default")
      (node (ref "SJ1") (pin "2") (pinfunction "2_2") (pintype "passive"))
      (node (ref "U1") (pin "8") (pinfunction "PB8_8") (pintype "bidirectional"))
    )
    (net (code "17") (name "I2C_SCL_BUF_SENSE2") (class "Default")
      (node (ref "SJ2") (pin "2") (pinfunction "2_2") (pintype "passive"))
      (node (ref "U1") (pin "7") (pinfunction "PB7_7") (pintype "bidirectional"))
    )
    (net (code "18") (name "I2C_SCL_BUF_SENSE3") (class "Default")
      (node (ref "SJ3") (pin "2") (pinfunction "2_2") (pintype "passive"))
      (node (ref "U1") (pin "24") (pinfunction "PC15_24") (pintype "bidirectional"))
    )
    (net (code "19") (name "I2C_SCL_BUF_SENSE4") (class "Default")
      (node (ref "SJ4") (pin "2") (pinfunction "2_2") (pintype "passive"))
      (node (ref "U1") (pin "23") (pinfunction "PC14_23") (pintype "bidirectional"))
    )
    (net (code "20") (name "I2C_SDA") (class "Default")
      (node (ref "CON1") (pin "2") (pinfunction "S_2") (pintype "passive"))
      (node (ref "R2") (pin "1") (pinfunction "1_1") (pintype "passive"))
      (node (ref "U1") (pin "5") (pinfunction "PC0_5") (pintype "bidirectional"))
      (node (ref "U2") (pin "6") (pinfunction "SDAIN_6") (pintype "bidirectional"))
      (node (ref "U3") (pin "6") (pinfunction "SDAIN_6") (pintype "bidirectional"))
      (node (ref "U4") (pin "6") (pinfunction "SDAIN_6") (pintype "bidirectional"))
      (node (ref "U5") (pin "6") (pinfunction "SDAIN_6") (pintype "bidirectional"))
    )
    (net (code "21") (name "I2C_SDA_BUF1") (class "Default")
      (node (ref "CON2") (pin "1") (pinfunction "S_1") (pintype "passive"))
      (node (ref "R13") (pin "1") (pinfunction "1_1") (pintype "passive"))
      (node (ref "U2") (pin "7") (pinfunction "SDAOUT_7") (pintype "bidirectional"))
    )
    (net (code "22") (name "I2C_SDA_BUF2") (class "Default")
      (node (ref "CON3") (pin "1") (pinfunction "S_1") (pintype "passive"))
      (node (ref "R14") (pin "1") (pinfunction "1_1") (pintype "passive"))
      (node (ref "U3") (pin "7") (pinfunction "SDAOUT_7") (pintype "bidirectional"))
    )
    (net (code "23") (name "I2C_SDA_BUF3") (class "Default")
      (node (ref "CON4") (pin "1") (pinfunction "S_1") (pintype "passive"))
      (node (ref "R15") (pin "1") (pinfunction "1_1") (pintype "passive"))
      (node (ref "U4") (pin "7") (pinfunction "SDAOUT_7") (pintype "bidirectional"))
    )
    (net (code "24") (name "I2C_SDA_BUF4") (class "Default")
      (node (ref "CON5") (pin "1") (pinfunction "S_1") (pintype "passive"))
      (node (ref "R16") (pin "1") (pinfunction "1_1") (pintype "passive"))
      (node (ref "U5") (pin "7") (pinfunction "SDAOUT_7") (pintype "bidirectional"))
    )
    (net (code "25") (name "I2C_VBIAS1") (class "Default")
      (node (ref "C9") (pin "1") (pinfunction "C1_1") (pintype "passive"))
      (node (ref "R13") (pin "2") (pinfunction "2_2") (pintype "passive"))
      (node (ref "R17") (pin "2") (pinfunction "2_2") (pintype "passive"))
      (node (ref "U1") (pin "32") (pinfunction "PE13_32") (pintype "bidirectional"))
      (node (ref "U6") (pin "6") (pinfunction "VOUT_6") (pintype "bidirectional"))
    )
    (net (code "26") (name "I2C_VBIAS2") (class "Default")
      (node (ref "C10") (pin "1") (pinfunction "C1_1") (pintype "passive"))
      (node (ref "R14") (pin "2") (pinfunction "2_2") (pintype "passive"))
      (node (ref "R18") (pin "2") (pinfunction "2_2") (pintype "passive"))
      (node (ref "U1") (pin "3") (pinfunction "PA2_3") (pintype "bidirectional"))
      (node (ref "U7") (pin "6") (pinfunction "VOUT_6") (pintype "bidirectional"))
    )
    (net (code "27") (name "I2C_VBIAS3") (class "Default")
      (node (ref "C11") (pin "1") (pinfunction "C1_1") (pintype "passive"))
      (node (ref "R15") (pin "2") (pinfunction "2_2") (pintype "passive"))
      (node (ref "R19") (pin "2") (pinfunction "2_2") (pintype "passive"))
      (node (ref "U1") (pin "13") (pinfunction "PB14_13") (pintype "bidirectional"))
      (node (ref "U8") (pin "6") (pinfunction "VOUT_6") (pintype "bidirectional"))
    )
    (net (code "28") (name "I2C_VBIAS4") (class "Default")
      (node (ref "C12") (pin "1") (pinfunction "C1_1") (pintype "passive"))
      (node (ref "R16") (pin "2") (pinfunction "2_2") (pintype "passive"))
      (node (ref "R20") (pin "2") (pinfunction "2_2") (pintype "passive"))
      (node (ref "U1") (pin "18") (pinfunction "PD6_18") (pintype "bidirectional"))
      (node (ref "U9") (pin "6") (pinfunction "VOUT_6") (pintype "bidirectional"))
    )
    (net (code "29") (name "LED") (class "Default")
      (node (ref "R4") (pin "2") (pinfunction "2_2") (pintype "passive"))
      (node (ref "U1") (pin "29") (pinfunction "PE10_29") (pintype "bidirectional"))
    )
    (net (code "30") (name "Net-(C4-C1)") (class "Default")
      (node (ref "C4") (pin "1") (pinfunction "C1_1") (pintype "passive"))
      (node (ref "U1") (pin "21") (pinfunction "DECOUPLE_21") (pintype "bidirectional"))
    )
    (net (code "31") (name "Net-(D1-PadA)") (class "Default")
      (node (ref "D1") (pin "A") (pinfunction "A_A") (pintype "passive"))
      (node (ref "R4") (pin "1") (pinfunction "1_1") (pintype "passive"))
    )
    (net (code "32") (name "Net-(D6-PadA)") (class "Default")
      (node (ref "D6") (pin "A") (pinfunction "A_A") (pintype "passive"))
      (node (ref "R21") (pin "1") (pinfunction "1_1") (pintype "passive"))
    )
    (net (code "33") (name "Net-(D7-PadA)") (class "Default")
      (node (ref "D7") (pin "A") (pinfunction "A_A") (pintype "passive"))
      (node (ref "R22") (pin "1") (pinfunction "1_1") (pintype "passive"))
    )
    (net (code "34") (name "Net-(D8-PadA)") (class "Default")
      (node (ref "D8") (pin "A") (pinfunction "A_A") (pintype "passive"))
      (node (ref "R23") (pin "1") (pinfunction "1_1") (pintype "passive"))
    )
    (net (code "35") (name "Net-(D9-PadA)") (class "Default")
      (node (ref "D9") (pin "A") (pinfunction "A_A") (pintype "passive"))
      (node (ref "R24") (pin "1") (pinfunction "1_1") (pintype "passive"))
    )
    (net (code "36") (name "Net-(D10-PadA)") (class "Default")
      (node (ref "D10") (pin "A") (pinfunction "A_A") (pintype "passive"))
      (node (ref "R25") (pin "1") (pinfunction "1_1") (pintype "passive"))
    )
    (net (code "37") (name "Net-(U6-ILIMIT)") (class "Default")
      (node (ref "R9") (pin "2") (pinfunction "2_2") (pintype "passive"))
      (node (ref "U6") (pin "5") (pinfunction "ILIMIT_5") (pintype "bidirectional"))
    )
    (net (code "38") (name "Net-(U7-ILIMIT)") (class "Default")
      (node (ref "R10") (pin "2") (pinfunction "2_2") (pintype "passive"))
      (node (ref "U7") (pin "5") (pinfunction "ILIMIT_5") (pintype "bidirectional"))
    )
    (net (code "39") (name "Net-(U8-ILIMIT)") (class "Default")
      (node (ref "R11") (pin "2") (pinfunction "2_2") (pintype "passive"))
      (node (ref "U8") (pin "5") (pinfunction "ILIMIT_5") (pintype "bidirectional"))
    )
    (net (code "40") (name "Net-(U9-ILIMIT)") (class "Default")
      (node (ref "R12") (pin "2") (pinfunction "2_2") (pintype "passive"))
      (node (ref "U9") (pin "5") (pinfunction "ILIMIT_5") (pintype "bidirectional"))
    )
    (net (code "41") (name "SWCLK") (class "Default")
      (node (ref "TC1") (pin "4") (pinfunction "S_4") (pintype "passive"))
      (node (ref "U1") (pin "25") (pinfunction "PF0_25") (pintype "bidirectional"))
    )
    (net (code "42") (name "SWDIO") (class "Default")
      (node (ref "TC1") (pin "2") (pinfunction "S_2") (pintype "passive"))
      (node (ref "U1") (pin "26") (pinfunction "PF1_26") (pintype "bidirectional"))
    )
    (net (code "43") (name "SWO") (class "Default")
      (node (ref "TC1") (pin "6") (pinfunction "S_6") (pintype "passive"))
      (node (ref "U1") (pin "27") (pinfunction "PF2_27") (pintype "bidirectional"))
    )
    (net (code "44") (name "unconnected-(TC1F-S-Pad5)") (class "Default")
      (node (ref "TC1") (pin "5") (pinfunction "S_5") (pintype "passive"))
    )
    (net (code "45") (name "unconnected-(U1-PD7-Pad19)") (class "Default")
      (node (ref "U1") (pin "19") (pinfunction "PD7_19") (pintype "bidirectional"))
    )
    (net (code "46") (name "unconnected-(U1-PE11-Pad30)") (class "Default")
      (node (ref "U1") (pin "30") (pinfunction "PE11_30") (pintype "bidirectional"))
    )
    (net (code "47") (name "unconnected-(U6-~{FAULT}-Pad4)") (class "Default")
      (node (ref "U6") (pin "4") (pinfunction "~{FAULT}_4") (pintype "bidirectional"))
    )
    (net (code "48") (name "unconnected-(U7-~{FAULT}-Pad4)") (class "Default")
      (node (ref "U7") (pin "4") (pinfunction "~{FAULT}_4") (pintype "bidirectional"))
    )
    (net (code "49") (name "unconnected-(U8-~{FAULT}-Pad4)") (class "Default")
      (node (ref "U8") (pin "4") (pinfunction "~{FAULT}_4") (pintype "bidirectional"))
    )
    (net (code "50") (name "unconnected-(U9-~{FAULT}-Pad4)") (class "Default")
      (node (ref "U9") (pin "4") (pinfunction "~{FAULT}_4") (pintype "bidirectional"))
    )
    (net (code "51") (name "~{RESET}") (class "Default")
      (node (ref "R1") (pin "1") (pinfunction "1_1") (pintype "passive"))
      (node (ref "TC1") (pin "10") (pinfunction "S_10") (pintype "passive"))
      (node (ref "U1") (pin "9") (pinfunction "~{RESET}_9") (pintype "bidirectional"))
    )
  )
)
